# Power_Board.net
KiCad netlist of a schematic drawn in EAGLE
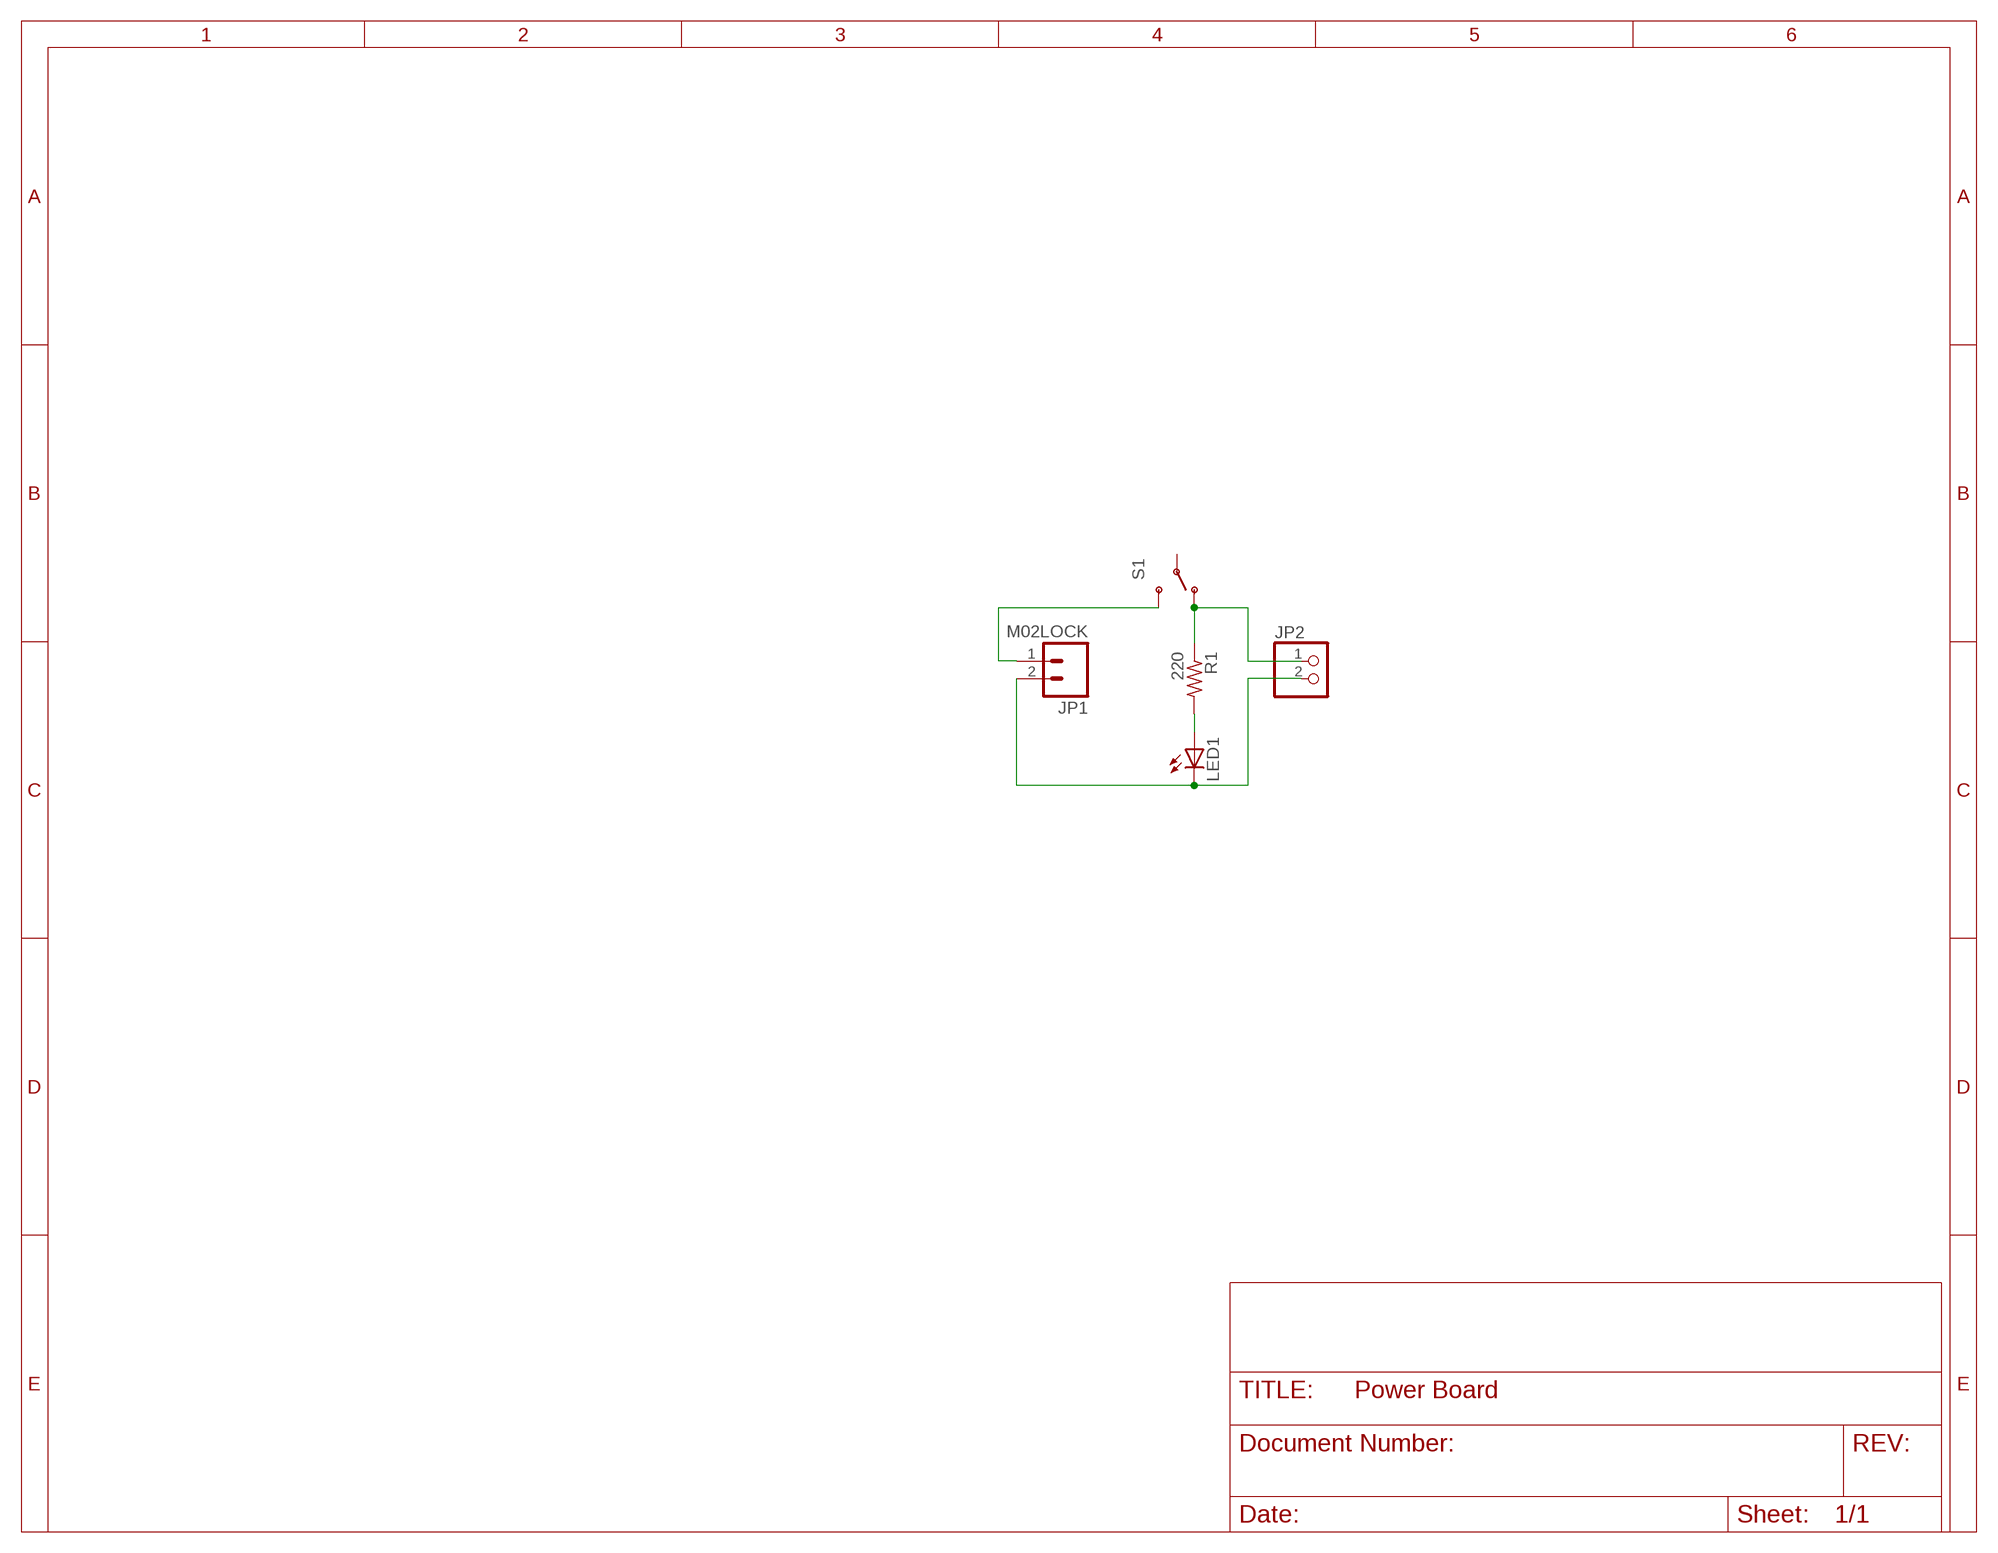
[diagram p0: schematic, sheet 1]

(export (version "E")
  (design (tool "Eeschema 10.0.6"))
  (components
    (comp (ref "JP1")
      (value "M02LOCK")
      (footprint "eagle-import:1X02_LOCK")
      (libsource (lib "eagle-import") (part "M02LOCK"))
    )
    (comp (ref "JP2")
      (value "PINHD-1X2")
      (footprint "eagle-import:1X02")
      (libsource (lib "eagle-import") (part "PINHD-1X2"))
    )
    (comp (ref "LED1")
      (value "LED3MM")
      (footprint "eagle-import:LED3MM")
      (libsource (lib "eagle-import") (part "LED3MM"))
    )
    (comp (ref "R1")
      (value "220")
      (footprint "eagle-import:0204_5")
      (libsource (lib "eagle-import") (part "R-US_0204/5"))
    )
    (comp (ref "S1")
      (value "SWITCH-SPDTPTH")
      (footprint "eagle-import:SWITCH-SPDT")
      (libsource (lib "eagle-import") (part "SWITCH-SPDTPTH"))
    )
  )
  (nets
    (net (code "1") (name "Net-(LED1-C)") (class "Default")
      (node (ref "JP1") (pin "2") (pinfunction "2_2") (pintype "passive"))
      (node (ref "JP2") (pin "2") (pinfunction "2_2") (pintype "passive"))
      (node (ref "LED1") (pin "K") (pinfunction "C_K") (pintype "passive"))
    )
    (net (code "2") (name "Net-(LED1-PadA)") (class "Default")
      (node (ref "LED1") (pin "A") (pinfunction "A_A") (pintype "passive"))
      (node (ref "R1") (pin "2") (pinfunction "2_2") (pintype "passive"))
    )
    (net (code "3") (name "Net-(S1-O)") (class "Default")
      (node (ref "JP2") (pin "1") (pinfunction "1_1") (pintype "passive"))
      (node (ref "R1") (pin "1") (pinfunction "1_1") (pintype "passive"))
      (node (ref "S1") (pin "1") (pinfunction "O_1") (pintype "passive"))
    )
    (net (code "4") (name "Net-(S1-S)") (class "Default")
      (node (ref "JP1") (pin "1") (pinfunction "1_1") (pintype "passive"))
      (node (ref "S1") (pin "3") (pinfunction "S_3") (pintype "passive"))
    )
    (net (code "5") (name "unconnected-(S1-P-Pad2)") (class "Default")
      (node (ref "S1") (pin "2") (pinfunction "P_2") (pintype "passive"))
    )
  )
)
